# DM2080_USB.net
KiCad netlist of a schematic drawn in Altium Designer
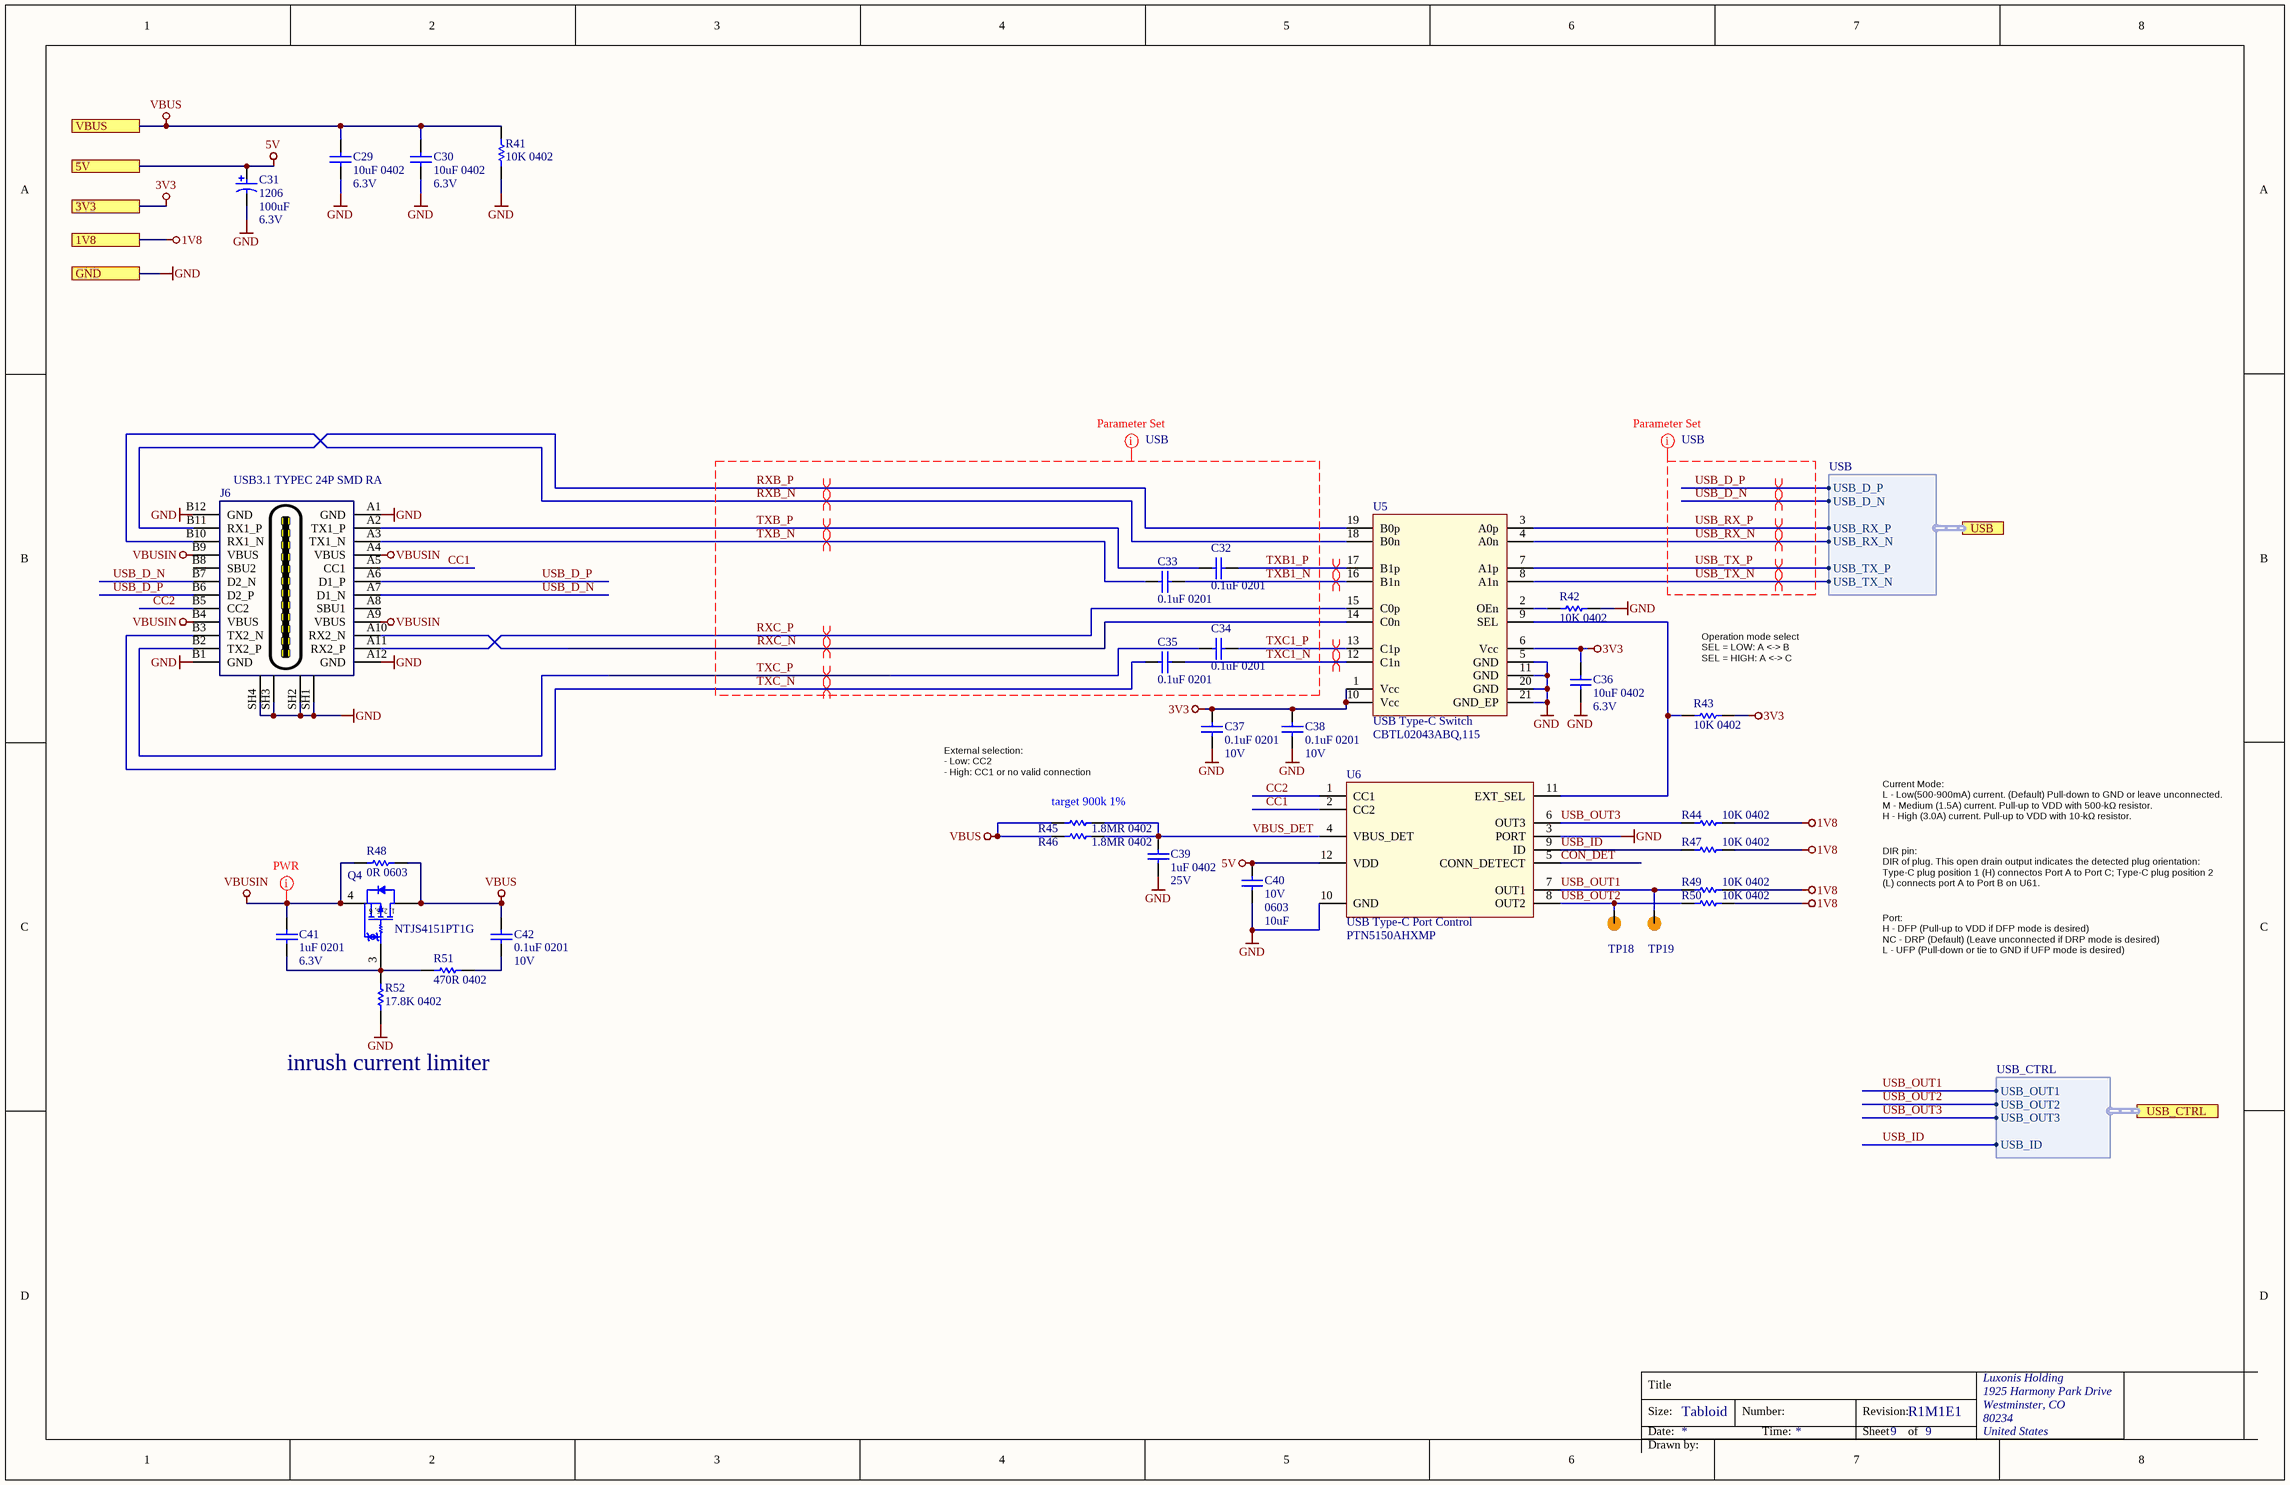
[diagram p0: DM2080_USB.SchDoc]

(export (version "E")
  (design (tool "Eeschema 10.0.6"))
  (components
    (comp (ref "C29")
      (value "10uF 0402")
      (footprint "CAP_Altium_Vault_Generic:CAPC0402(1005)70_L")
      (description "CAP CER 10UF 6.3V X5R 0402 20%")
      (fields (field (name "TOLERANCE") "20%") (field (name "VOLTAGE RATING") "6.3V"))
      (libsource (lib "LuxonisMaster") (part "GRM155R60J106ME15D"))
    )
    (comp (ref "C30")
      (value "10uF 0402")
      (footprint "CAP_Altium_Vault_Generic:CAPC0402(1005)70_L")
      (description "CAP CER 10UF 6.3V X5R 0402 20%")
      (fields (field (name "TOLERANCE") "20%") (field (name "VOLTAGE RATING") "6.3V"))
      (libsource (lib "LuxonisMaster") (part "GRM155R60J106ME15D"))
    )
    (comp (ref "C31")
      (value "100uF 1206 6V3 tantal")
      (footprint "RESTL1206(3216)_L")
      (fields
        (field (name "SIZE CODE") "1206")
        (field (name "CAPACITANCE") "100uF")
        (field (name "RATED DC VOLTAGE (URDC)") "6.3V")
      )
      (libsource (lib "DM1098LUXD-LITE") (part "TLJA107M006R0500"))
    )
    (comp (ref "C32")
      (value "0.1uF 0201")
      (footprint "CAP_Altium_Vault_Generic:CAPC0201(0603)33_L")
      (description "CAP CER 0.1UF 10V X5R 0201")
      (fields (field (name "TOLERANCE") "10%") (field (name "VOLTAGE") "10V"))
      (libsource (lib "LuxonisMaster") (part "GRM033R61A104KE15D"))
    )
    (comp (ref "C33")
      (value "0.1uF 0201")
      (footprint "CAP_Altium_Vault_Generic:CAPC0201(0603)33_L")
      (description "CAP CER 0.1UF 10V X5R 0201")
      (fields (field (name "TOLERANCE") "10%") (field (name "VOLTAGE") "10V"))
      (libsource (lib "LuxonisMaster") (part "GRM033R61A104KE15D"))
    )
    (comp (ref "C34")
      (value "0.1uF 0201")
      (footprint "CAP_Altium_Vault_Generic:CAPC0201(0603)33_L")
      (description "CAP CER 0.1UF 10V X5R 0201")
      (fields (field (name "TOLERANCE") "10%") (field (name "VOLTAGE") "10V"))
      (libsource (lib "LuxonisMaster") (part "GRM033R61A104KE15D"))
    )
    (comp (ref "C35")
      (value "0.1uF 0201")
      (footprint "CAP_Altium_Vault_Generic:CAPC0201(0603)33_L")
      (description "CAP CER 0.1UF 10V X5R 0201")
      (fields (field (name "TOLERANCE") "10%") (field (name "VOLTAGE") "10V"))
      (libsource (lib "LuxonisMaster") (part "GRM033R61A104KE15D"))
    )
    (comp (ref "C36")
      (value "10uF 0402")
      (footprint "CAP_Altium_Vault_Generic:CAPC0402(1005)70_L")
      (description "CAP CER 10UF 6.3V X5R 0402 20%")
      (fields (field (name "TOLERANCE") "20%") (field (name "VOLTAGE RATING") "6.3V"))
      (libsource (lib "LuxonisMaster") (part "GRM155R60J106ME15D"))
    )
    (comp (ref "C37")
      (value "0.1uF 0201")
      (footprint "CAP_Altium_Vault_Generic:CAPC0201(0603)33_L")
      (description "CAP CER 0.1UF 10V X5R 0201")
      (fields (field (name "TOLERANCE") "10%") (field (name "VOLTAGE") "10V"))
      (libsource (lib "LuxonisMaster") (part "GRM033R61A104KE15D"))
    )
    (comp (ref "C38")
      (value "0.1uF 0201")
      (footprint "CAP_Altium_Vault_Generic:CAPC0201(0603)33_L")
      (description "CAP CER 0.1UF 10V X5R 0201")
      (fields (field (name "TOLERANCE") "10%") (field (name "VOLTAGE") "10V"))
      (libsource (lib "LuxonisMaster") (part "GRM033R61A104KE15D"))
    )
    (comp (ref "C39")
      (value "1uF 0402")
      (footprint "CAP_Altium_Vault_Generic:CAPC0402(1005)70_L")
      (description "CAP CER 1UF 25V X5R 0402 10%")
      (fields
        (field (name "TOLERANCE") "10%")
        (field (name "VOLTAGE") "25V")
        (field (name "VOLTAGE RATING") "25V")
      )
      (libsource (lib "LuxonisMaster") (part "GRM155R61E105KA12D"))
    )
    (comp (ref "C40")
      (value "GRM188R61A106ME69D")
      (footprint "CAPC0603(1608)100_L")
      (description "CAP CER 10UF 10V X5R 0603 20%")
      (fields
        (field (name "VOLTAGE RATING") "10V")
        (field (name "CASE/PACKAGE") "0603")
        (field (name "TOLERANCE") "20%")
        (field (name "CAPACITANCE") "10uF")
      )
      (libsource (lib "Luxonis LLC") (part "LLL153C70G474ME17E"))
    )
    (comp (ref "C41")
      (value "1uF 0201")
      (footprint "CAP_Altium_Vault_Generic:CAPC0201(0603)33_L")
      (description "CAP CER 1UF 6.3V X5R 0201 20%")
      (fields (field (name "TOLERANCE") "20%") (field (name "VOLTAGE") "6.3V"))
      (libsource (lib "LuxonisMaster") (part "GRM033R60J105MEA2D"))
    )
    (comp (ref "C42")
      (value "0.1uF 0201")
      (footprint "CAP_Altium_Vault_Generic:CAPC0201(0603)33_L")
      (description "CAP CER 0.1UF 10V X5R 0201")
      (fields (field (name "TOLERANCE") "10%") (field (name "VOLTAGE") "10V"))
      (libsource (lib "LuxonisMaster") (part "GRM033R61A104KE15D"))
    )
    (comp (ref "J6")
      (value "USB3.1 TYPEC 24P SMD RA")
      (footprint "LuxonisMaster:105450-0101")
      (description "CONN RCP USB3.1 TYPEC 24P SMD RA")
      (libsource (lib "LuxonisMaster") (part "105450-0101"))
    )
    (comp (ref "Q4")
      (value "NTJS4151PT1G")
      (footprint "ONSC-SC70-6-419B-02_W_V")
      (description "Trench Power MOSFET, -20 V, -4.2 A, Single P-Channel, 6-Pin SC70, Pb-Free, Tape and Reel")
      (libsource (lib "altium-import") (part "root_1_mirrored_NTJS4151PT1G_"))
    )
    (comp (ref "R41")
      (value "10K 0402")
      (footprint "RES_Altium_Vault_Generic:RESC0402(1005)_L")
      (fields (field (name "TOLERANCE") "1%"))
      (libsource (lib "LuxonisMaster") (part "RC0402FR-1310KL"))
    )
    (comp (ref "R42")
      (value "10K 0402")
      (footprint "RES_Altium_Vault_Generic:RESC0402(1005)_L")
      (fields (field (name "TOLERANCE") "1%"))
      (libsource (lib "LuxonisMaster") (part "RC0402FR-1310KL"))
    )
    (comp (ref "R43")
      (value "10K 0402")
      (footprint "RES_Altium_Vault_Generic:RESC0402(1005)_L")
      (fields (field (name "TOLERANCE") "1%"))
      (libsource (lib "LuxonisMaster") (part "RC0402FR-1310KL"))
    )
    (comp (ref "R44")
      (value "10K 0402")
      (footprint "RES_Altium_Vault_Generic:RESC0402(1005)_L")
      (fields (field (name "TOLERANCE") "1%"))
      (libsource (lib "LuxonisMaster") (part "RC0402FR-1310KL"))
    )
    (comp (ref "R45")
      (value "1.8MR 0402")
      (footprint "RES_Altium_Vault_Generic:RESC0402(1005)_L")
      (description "RES SMD 1.8M OHM 1% 1/16W 0402")
      (fields (field (name "TOLERANCE") "1%"))
      (libsource (lib "LuxonisMaster") (part "CRCW04021M80FKED"))
    )
    (comp (ref "R46")
      (value "1.8MR 0402")
      (footprint "RES_Altium_Vault_Generic:RESC0402(1005)_L")
      (description "RES SMD 1.8M OHM 1% 1/16W 0402")
      (fields (field (name "TOLERANCE") "1%"))
      (libsource (lib "LuxonisMaster") (part "CRCW04021M80FKED"))
    )
    (comp (ref "R47")
      (value "10K 0402")
      (footprint "RES_Altium_Vault_Generic:RESC0402(1005)_L")
      (fields (field (name "TOLERANCE") "1%"))
      (libsource (lib "LuxonisMaster") (part "RC0402FR-1310KL"))
    )
    (comp (ref "R48")
      (value "0R 0603")
      (footprint "RES_Altium_Vault_Generic:RESC0603(1608)_N")
      (fields (field (name "TOLERANCE") "5%"))
      (libsource (lib "LuxonisMaster") (part "CRCW06030000Z0EA"))
    )
    (comp (ref "R49")
      (value "10K 0402")
      (footprint "RES_Altium_Vault_Generic:RESC0402(1005)_L")
      (fields (field (name "TOLERANCE") "1%"))
      (libsource (lib "LuxonisMaster") (part "RC0402FR-1310KL"))
    )
    (comp (ref "R50")
      (value "10K 0402")
      (footprint "RES_Altium_Vault_Generic:RESC0402(1005)_L")
      (fields (field (name "TOLERANCE") "1%"))
      (libsource (lib "LuxonisMaster") (part "RC0402FR-1310KL"))
    )
    (comp (ref "R51")
      (value "470R 0402")
      (footprint "RES_Altium_Vault_Generic:RESC0402(1005)_L")
      (description "RES SMD 470 OHM 1% 1/16W 0402")
      (fields (field (name "TOLERANCE") "1%"))
      (libsource (lib "LuxonisMaster") (part "CRCW0402470RFKED"))
    )
    (comp (ref "R52")
      (value "17.8K 0402")
      (footprint "RES_Altium_Vault_Generic:RESC0402(1005)_L")
      (fields (field (name "TOLERANCE") "1%"))
      (libsource (lib "LuxonisMaster") (part "ERJ-2RKF1782X"))
    )
    (comp (ref "TP18")
      (value "TP100_200_NS")
      (footprint "LuxonisMaster:TP100_200_NS")
      (libsource (lib "LuxonisMaster") (part "TEST_POINT"))
    )
    (comp (ref "TP19")
      (value "TP100_200_NS")
      (footprint "LuxonisMaster:TP100_200_NS")
      (libsource (lib "LuxonisMaster") (part "TEST_POINT"))
    )
    (comp (ref "U5")
      (value "USB Type-C Switch")
      (footprint "CBTL02043A")
      (fields (field (name "MANUFACTURER PART NUMBER 1") "CBTL02043ABQ,115"))
      (libsource (lib "DM1099") (part "CBTL02043A"))
    )
    (comp (ref "U6")
      (value "USB Type-C Port Control")
      (footprint "PTN5150H")
      (description "Power Supply Support Circuit, Fixed, 2 Channel, 0.2, PQCC12")
      (fields (field (name "MANUFACTURER PART NUMBER 1") "PTN5150AHXMP"))
      (libsource (lib "DM1099") (part "PTN5150A"))
    )
  )
  (nets
    (net (code "3") (name "/CC1") (class "Default")
      (node (ref "J6") (pin "A5") (pinfunction "CC1_A5") (pintype "passive"))
      (node (ref "U6") (pin "2") (pinfunction "CC2_2") (pintype "passive"))
    )
    (net (code "4") (name "/CC2") (class "Default")
      (node (ref "J6") (pin "B5") (pinfunction "CC2_B5") (pintype "passive"))
      (node (ref "U6") (pin "1") (pinfunction "CC1_1") (pintype "passive"))
    )
    (net (code "5") (name "/CON_DET") (class "Default")
      (node (ref "U6") (pin "5") (pinfunction "CONN_DETECT_5") (pintype "passive"))
    )
    (net (code "6") (name "/RXB_N") (class "Default")
      (node (ref "J6") (pin "B10") (pinfunction "RX1_N_B10") (pintype "passive"))
      (node (ref "U5") (pin "18") (pinfunction "B0n_18") (pintype "passive"))
    )
    (net (code "7") (name "/RXB_P") (class "Default")
      (node (ref "J6") (pin "B11") (pinfunction "RX1_P_B11") (pintype "passive"))
      (node (ref "U5") (pin "19") (pinfunction "B0p_19") (pintype "passive"))
    )
    (net (code "8") (name "/RXC_N") (class "Default")
      (node (ref "J6") (pin "A10") (pinfunction "RX2_N_A10") (pintype "passive"))
      (node (ref "U5") (pin "14") (pinfunction "C0n_14") (pintype "passive"))
    )
    (net (code "9") (name "/RXC_P") (class "Default")
      (node (ref "J6") (pin "A11") (pinfunction "RX2_P_A11") (pintype "passive"))
      (node (ref "U5") (pin "15") (pinfunction "C0p_15") (pintype "passive"))
    )
    (net (code "10") (name "/TXB1_N") (class "Default")
      (node (ref "C33") (pin "2") (pinfunction "2_2") (pintype "passive"))
      (node (ref "U5") (pin "16") (pinfunction "B1n_16") (pintype "passive"))
    )
    (net (code "11") (name "/TXB1_P") (class "Default")
      (node (ref "C32") (pin "2") (pinfunction "2_2") (pintype "passive"))
      (node (ref "U5") (pin "17") (pinfunction "B1p_17") (pintype "passive"))
    )
    (net (code "12") (name "/TXB_N") (class "Default")
      (node (ref "C33") (pin "1") (pinfunction "1_1") (pintype "passive"))
      (node (ref "J6") (pin "A3") (pinfunction "TX1_N_A3") (pintype "passive"))
    )
    (net (code "13") (name "/TXB_P") (class "Default")
      (node (ref "C32") (pin "1") (pinfunction "1_1") (pintype "passive"))
      (node (ref "J6") (pin "A2") (pinfunction "TX1_P_A2") (pintype "passive"))
    )
    (net (code "14") (name "/TXC1_N") (class "Default")
      (node (ref "C35") (pin "2") (pinfunction "2_2") (pintype "passive"))
      (node (ref "U5") (pin "12") (pinfunction "C1n_12") (pintype "passive"))
    )
    (net (code "15") (name "/TXC1_P") (class "Default")
      (node (ref "C34") (pin "2") (pinfunction "2_2") (pintype "passive"))
      (node (ref "U5") (pin "13") (pinfunction "C1p_13") (pintype "passive"))
    )
    (net (code "16") (name "/TXC_N") (class "Default")
      (node (ref "C35") (pin "1") (pinfunction "1_1") (pintype "passive"))
      (node (ref "J6") (pin "B3") (pinfunction "TX2_N_B3") (pintype "passive"))
    )
    (net (code "17") (name "/TXC_P") (class "Default")
      (node (ref "C34") (pin "1") (pinfunction "1_1") (pintype "passive"))
      (node (ref "J6") (pin "B2") (pinfunction "TX2_P_B2") (pintype "passive"))
    )
    (net (code "18") (name "/USB_D_N") (class "Default")
      (node (ref "J6") (pin "A7") (pinfunction "D1_N_A7") (pintype "passive"))
      (node (ref "J6") (pin "B7") (pinfunction "D2_N_B7") (pintype "passive"))
    )
    (net (code "19") (name "/USB_D_P") (class "Default")
      (node (ref "J6") (pin "A6") (pinfunction "D1_P_A6") (pintype "passive"))
      (node (ref "J6") (pin "B6") (pinfunction "D2_P_B6") (pintype "passive"))
    )
    (net (code "20") (name "/USB_ID") (class "Default")
      (node (ref "R47") (pin "1") (pinfunction "1_1") (pintype "passive"))
      (node (ref "U6") (pin "9") (pinfunction "ID_9") (pintype "passive"))
    )
    (net (code "21") (name "/USB_OUT1") (class "Default")
      (node (ref "R49") (pin "1") (pinfunction "1_1") (pintype "passive"))
      (node (ref "TP19") (pin "1") (pintype "passive"))
      (node (ref "U6") (pin "7") (pinfunction "OUT1_7") (pintype "passive"))
    )
    (net (code "22") (name "/USB_OUT2") (class "Default")
      (node (ref "R50") (pin "1") (pinfunction "1_1") (pintype "passive"))
      (node (ref "TP18") (pin "1") (pintype "passive"))
      (node (ref "U6") (pin "8") (pinfunction "OUT2_8") (pintype "passive"))
    )
    (net (code "23") (name "/USB_OUT3") (class "Default")
      (node (ref "R44") (pin "1") (pinfunction "1_1") (pintype "passive"))
      (node (ref "U6") (pin "6") (pinfunction "OUT3_6") (pintype "passive"))
    )
    (net (code "24") (name "/USB_RX_N") (class "Default")
      (node (ref "U5") (pin "4") (pinfunction "A0n_4") (pintype "passive"))
    )
    (net (code "25") (name "/USB_RX_P") (class "Default")
      (node (ref "U5") (pin "3") (pinfunction "A0p_3") (pintype "passive"))
    )
    (net (code "26") (name "/USB_TX_N") (class "Default")
      (node (ref "U5") (pin "8") (pinfunction "A1n_8") (pintype "passive"))
    )
    (net (code "27") (name "/USB_TX_P") (class "Default")
      (node (ref "U5") (pin "7") (pinfunction "A1p_7") (pintype "passive"))
    )
    (net (code "28") (name "/VBUS_DET") (class "Default")
      (node (ref "C39") (pin "2") (pinfunction "2_2") (pintype "passive"))
      (node (ref "R45") (pin "2") (pinfunction "2_2") (pintype "passive"))
      (node (ref "R46") (pin "2") (pinfunction "2_2") (pintype "passive"))
      (node (ref "U6") (pin "4") (pinfunction "VBUS_DET_4") (pintype "passive"))
    )
    (net (code "31") (name "1V8") (class "Default")
      (node (ref "R44") (pin "2") (pinfunction "2_2") (pintype "passive"))
      (node (ref "R47") (pin "2") (pinfunction "2_2") (pintype "passive"))
      (node (ref "R49") (pin "2") (pinfunction "2_2") (pintype "passive"))
      (node (ref "R50") (pin "2") (pinfunction "2_2") (pintype "passive"))
    )
    (net (code "32") (name "3V3") (class "Default")
      (node (ref "C36") (pin "2") (pinfunction "2_2") (pintype "passive"))
      (node (ref "C37") (pin "2") (pinfunction "2_2") (pintype "passive"))
      (node (ref "C38") (pin "2") (pinfunction "2_2") (pintype "passive"))
      (node (ref "R43") (pin "2") (pinfunction "2_2") (pintype "passive"))
      (node (ref "U5") (pin "1") (pinfunction "Vcc_1") (pintype "passive"))
      (node (ref "U5") (pin "10") (pinfunction "Vcc_10") (pintype "passive"))
      (node (ref "U5") (pin "6") (pinfunction "Vcc_6") (pintype "passive"))
    )
    (net (code "33") (name "5V") (class "Default")
      (node (ref "C31") (pin "1") (pinfunction "1_1") (pintype "passive"))
      (node (ref "C40") (pin "2") (pinfunction "2_2") (pintype "passive"))
      (node (ref "U6") (pin "12") (pinfunction "VDD_12") (pintype "passive"))
    )
    (net (code "34") (name "GND") (class "Default")
      (node (ref "C29") (pin "1") (pinfunction "1_1") (pintype "passive"))
      (node (ref "C30") (pin "1") (pinfunction "1_1") (pintype "passive"))
      (node (ref "C31") (pin "2") (pinfunction "2_2") (pintype "passive"))
      (node (ref "C36") (pin "1") (pinfunction "1_1") (pintype "passive"))
      (node (ref "C37") (pin "1") (pinfunction "1_1") (pintype "passive"))
      (node (ref "C38") (pin "1") (pinfunction "1_1") (pintype "passive"))
      (node (ref "C39") (pin "1") (pinfunction "1_1") (pintype "passive"))
      (node (ref "C40") (pin "1") (pinfunction "1_1") (pintype "passive"))
      (node (ref "J6") (pin "A1") (pinfunction "GND_A1") (pintype "passive"))
      (node (ref "J6") (pin "A12") (pinfunction "GND_A12") (pintype "passive"))
      (node (ref "J6") (pin "B1") (pinfunction "GND_B1") (pintype "passive"))
      (node (ref "J6") (pin "B12") (pinfunction "GND_B12") (pintype "passive"))
      (node (ref "J6") (pin "SH1") (pinfunction "SH_SH1") (pintype "passive"))
      (node (ref "J6") (pin "SH2") (pinfunction "SH_SH2") (pintype "passive"))
      (node (ref "J6") (pin "SH3") (pinfunction "SH_SH3") (pintype "passive"))
      (node (ref "J6") (pin "SH4") (pinfunction "SH_SH4") (pintype "passive"))
      (node (ref "R41") (pin "1") (pinfunction "1_1") (pintype "passive"))
      (node (ref "R42") (pin "2") (pinfunction "2_2") (pintype "passive"))
      (node (ref "R52") (pin "1") (pinfunction "1_1") (pintype "passive"))
      (node (ref "U5") (pin "11") (pinfunction "GND_11") (pintype "passive"))
      (node (ref "U5") (pin "20") (pinfunction "GND_20") (pintype "passive"))
      (node (ref "U5") (pin "21") (pinfunction "GND_EP_21") (pintype "passive"))
      (node (ref "U5") (pin "5") (pinfunction "GND_5") (pintype "passive"))
      (node (ref "U6") (pin "10") (pinfunction "GND_10") (pintype "passive"))
      (node (ref "U6") (pin "3") (pinfunction "PORT_3") (pintype "passive"))
    )
    (net (code "35") (name "Net-(C42-Pad1)") (class "Default")
      (node (ref "C42") (pin "1") (pinfunction "1_1") (pintype "passive"))
      (node (ref "R51") (pin "2") (pinfunction "2_2") (pintype "passive"))
    )
    (net (code "36") (name "Net-(Q4-G)") (class "Default")
      (node (ref "C41") (pin "1") (pinfunction "1_1") (pintype "passive"))
      (node (ref "Q4") (pin "3") (pinfunction "G_3") (pintype "passive"))
      (node (ref "R51") (pin "1") (pinfunction "1_1") (pintype "passive"))
      (node (ref "R52") (pin "2") (pinfunction "2_2") (pintype "passive"))
    )
    (net (code "37") (name "Net-(U5-OEn)") (class "Default")
      (node (ref "R42") (pin "1") (pinfunction "1_1") (pintype "passive"))
      (node (ref "U5") (pin "2") (pinfunction "OEn_2") (pintype "passive"))
    )
    (net (code "38") (name "Net-(U5-SEL)") (class "Default")
      (node (ref "R43") (pin "1") (pinfunction "1_1") (pintype "passive"))
      (node (ref "U5") (pin "9") (pinfunction "SEL_9") (pintype "passive"))
      (node (ref "U6") (pin "11") (pinfunction "EXT_SEL_11") (pintype "passive"))
    )
    (net (code "39") (name "VBUS") (class "Default")
      (node (ref "C29") (pin "2") (pinfunction "2_2") (pintype "passive"))
      (node (ref "C30") (pin "2") (pinfunction "2_2") (pintype "passive"))
      (node (ref "C42") (pin "2") (pinfunction "2_2") (pintype "passive"))
      (node (ref "Q4") (pin "1") (pinfunction "D_1") (pintype "passive"))
      (node (ref "Q4") (pin "2") (pinfunction "D_2") (pintype "passive"))
      (node (ref "Q4") (pin "5") (pinfunction "D_5") (pintype "passive"))
      (node (ref "Q4") (pin "6") (pinfunction "D_6") (pintype "passive"))
      (node (ref "R41") (pin "2") (pinfunction "2_2") (pintype "passive"))
      (node (ref "R45") (pin "1") (pinfunction "1_1") (pintype "passive"))
      (node (ref "R46") (pin "1") (pinfunction "1_1") (pintype "passive"))
      (node (ref "R48") (pin "2") (pinfunction "2_2") (pintype "passive"))
    )
    (net (code "40") (name "VBUSIN") (class "Default")
      (node (ref "C41") (pin "2") (pinfunction "2_2") (pintype "passive"))
      (node (ref "J6") (pin "A4") (pinfunction "VBUS_A4") (pintype "passive"))
      (node (ref "J6") (pin "A9") (pinfunction "VBUS_A9") (pintype "passive"))
      (node (ref "J6") (pin "B4") (pinfunction "VBUS_B4") (pintype "passive"))
      (node (ref "J6") (pin "B9") (pinfunction "VBUS_B9") (pintype "passive"))
      (node (ref "Q4") (pin "4") (pinfunction "S_4") (pintype "passive"))
      (node (ref "R48") (pin "1") (pinfunction "1_1") (pintype "passive"))
    )
    (net (code "41") (name "unconnected-(J6-SBU1-PadA8)") (class "Default")
      (node (ref "J6") (pin "A8") (pinfunction "SBU1_A8") (pintype "passive"))
    )
    (net (code "42") (name "unconnected-(J6-SBU2-PadB8)") (class "Default")
      (node (ref "J6") (pin "B8") (pinfunction "SBU2_B8") (pintype "passive"))
    )
  )
)
